# EasyEDApro.net
KiCad netlist of a schematic drawn in EasyEDA Pro
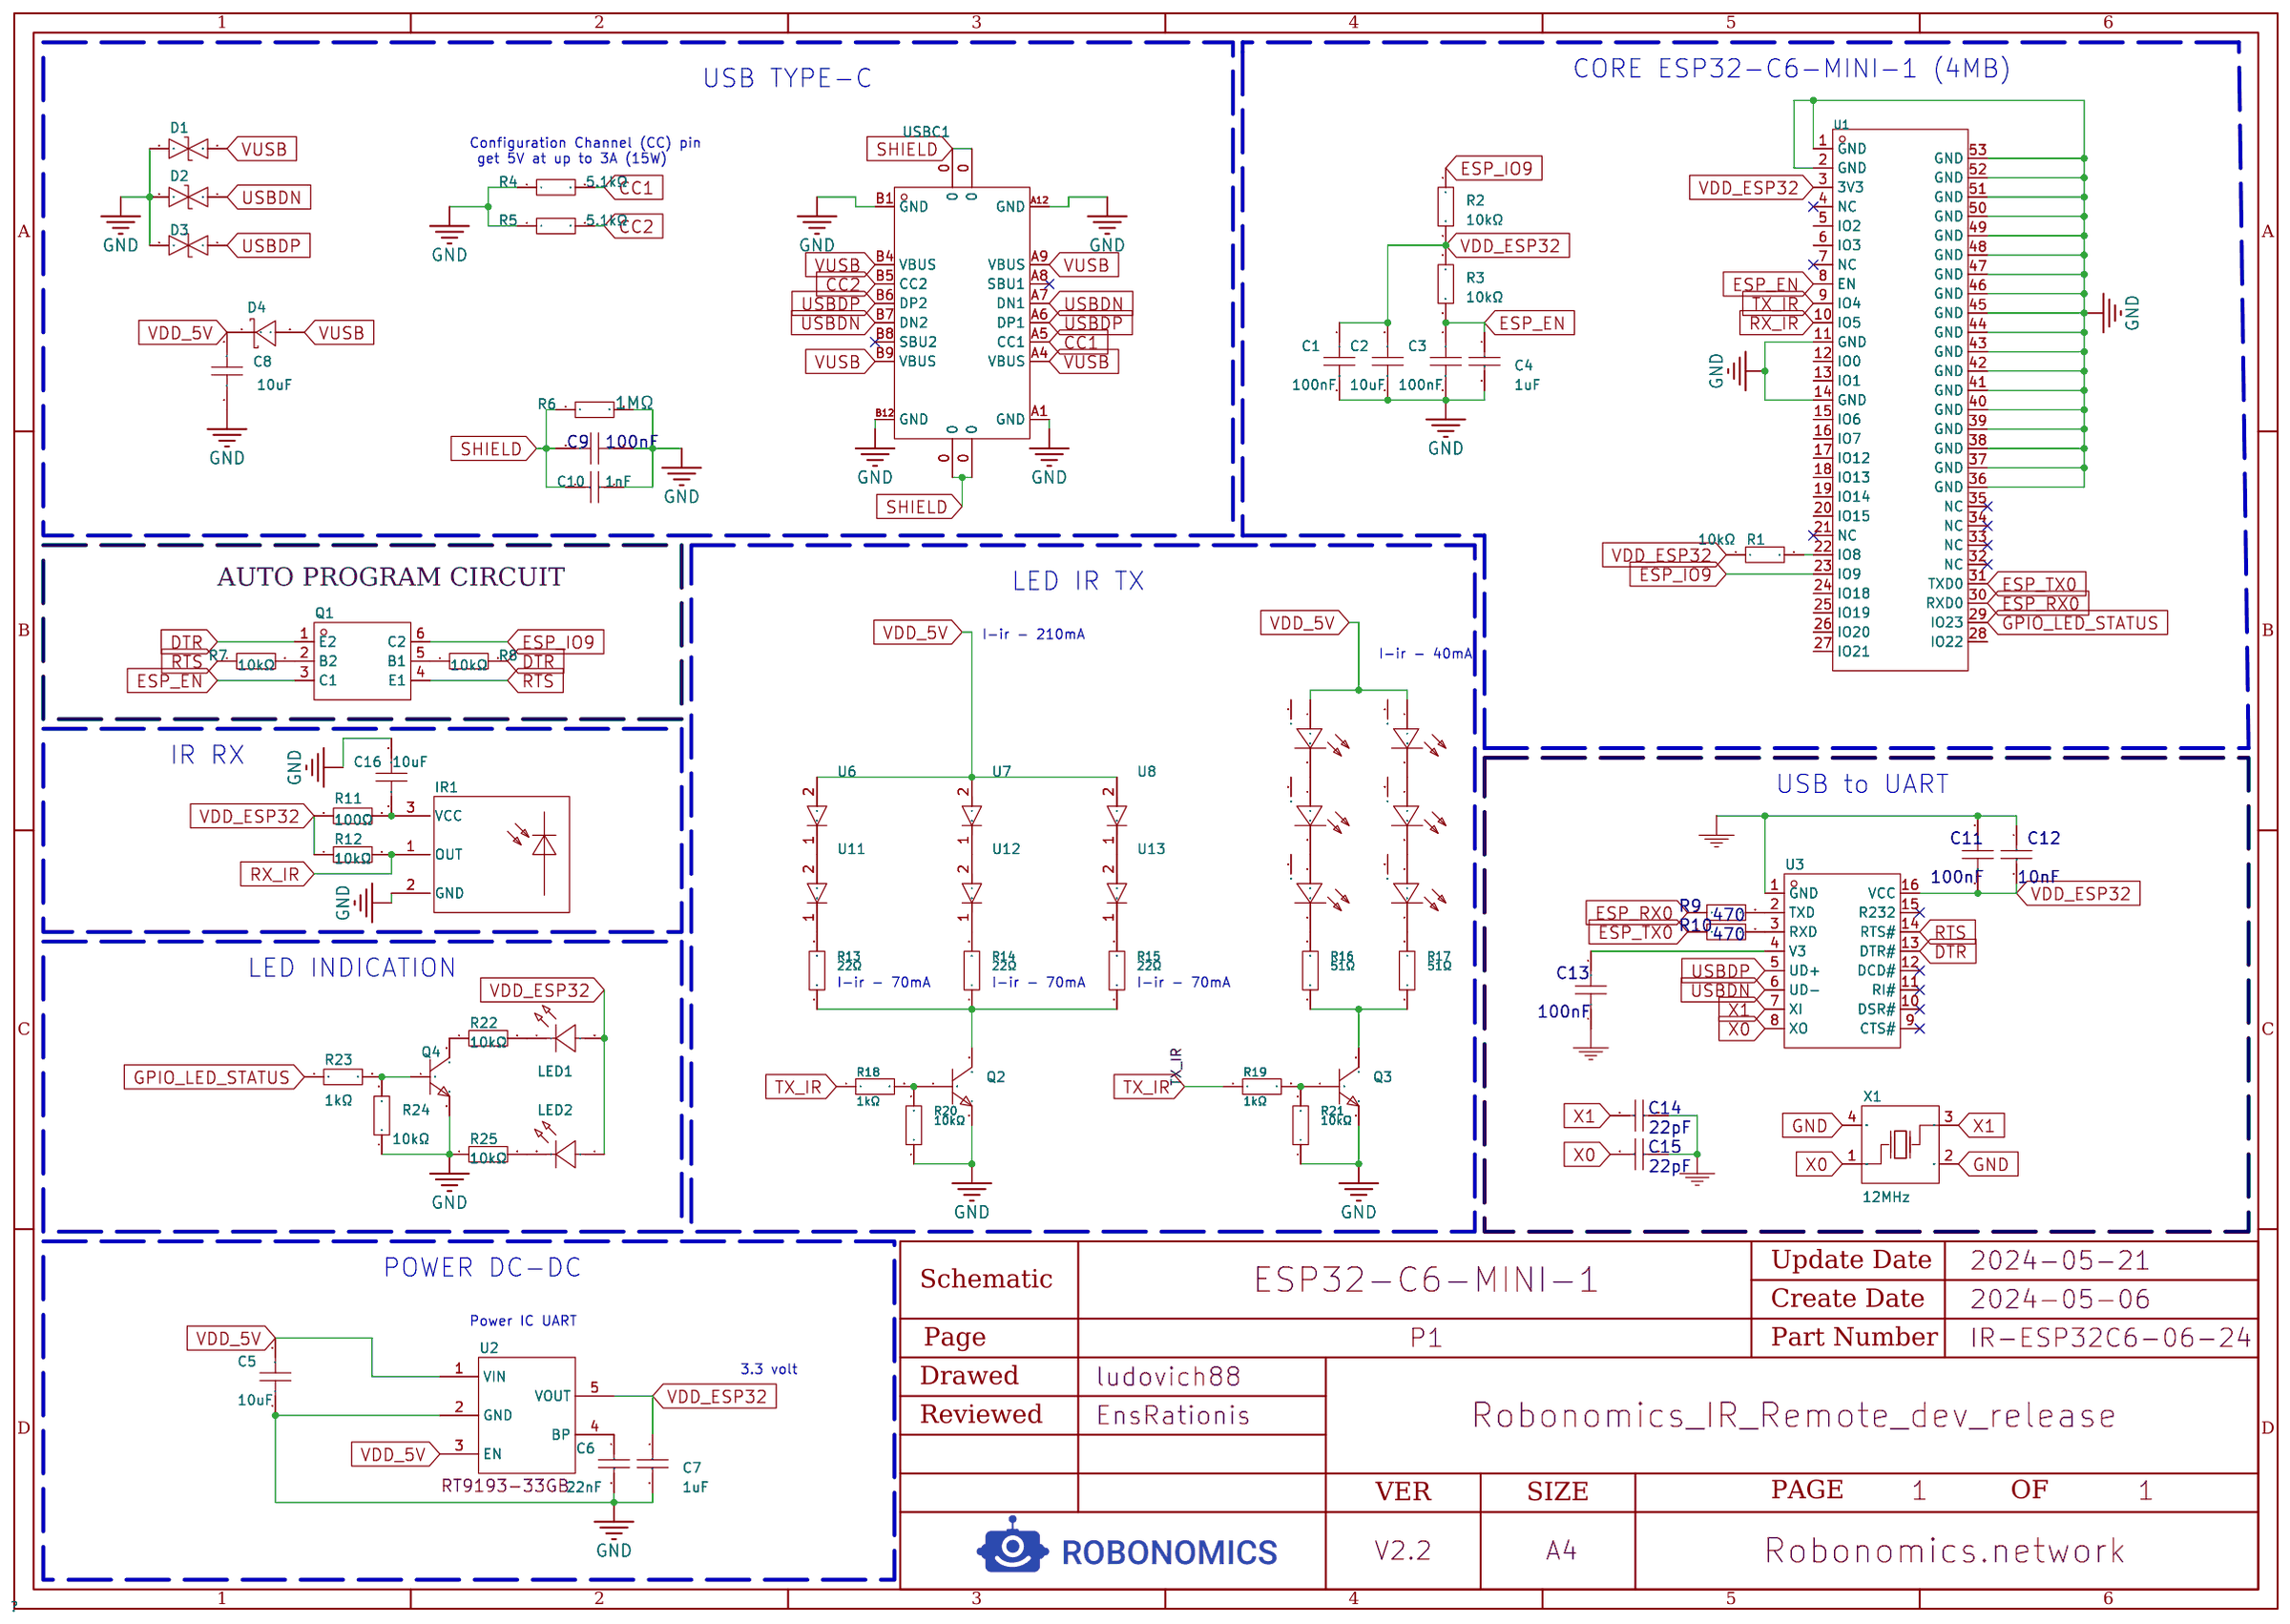
[diagram p0: schematic sheet]

(export (version "E")
  (design (tool "Eeschema 10.0.6"))
  (components
    (comp (ref "C1")
      (value "100nF")
      (fields
        (field (name "Manufacturer Part") "CC0603KRX7R9BB104")
        (field (name "Manufacturer") "YAGEO(国巨)")
      )
      (libsource (lib "easyedapro") (part "0603F104Z500"))
    )
    (comp (ref "C2")
      (value "10uF")
      (fields
        (field (name "Manufacturer Part") "CL10A106KP8NNNC")
        (field (name "Manufacturer") "SAMSUNG(三星)")
      )
      (libsource (lib "easyedapro") (part "CL10A106KP8NNNC"))
    )
    (comp (ref "C3")
      (value "100nF")
      (fields
        (field (name "Manufacturer Part") "CC0603KRX7R9BB104")
        (field (name "Manufacturer") "YAGEO(国巨)")
      )
      (libsource (lib "easyedapro") (part "0603F104Z500"))
    )
    (comp (ref "C4")
      (value "1uF")
      (footprint "easyedapro:C0603")
      (description "Capacitance:1uF Tolerance:±10% Tolerance:±10% Voltage Rated:50V Temperature Coefficient:X5R")
      (fields
        (field (name "Manufacturer Part") "CL10A105KB8NNNC")
        (field (name "Manufacturer") "SAMSUNG(三星)")
      )
      (libsource (lib "easyedapro") (part "CL10A105KB8NNNC"))
    )
    (comp (ref "C5")
      (value "10uF")
      (fields
        (field (name "Manufacturer Part") "CL10A106KP8NNNC")
        (field (name "Manufacturer") "SAMSUNG(三星)")
      )
      (libsource (lib "easyedapro") (part "CL10A106KP8NNNC"))
    )
    (comp (ref "C6")
      (value "22nF")
      (footprint "easyedapro:C0603")
      (description "Capacitance:22nF Tolerance:±10% Tolerance:±10% Voltage Rated:50V Temperature Coefficient:X7R")
      (fields
        (field (name "Manufacturer Part") "CL10B223KB8NNNC")
        (field (name "Manufacturer") "SAMSUNG(三星)")
      )
      (libsource (lib "easyedapro") (part "CL10B223KB8NNNC"))
    )
    (comp (ref "C7")
      (value "1uF")
      (footprint "easyedapro:C0603")
      (description "Capacitance:1uF Tolerance:±10% Tolerance:±10% Voltage Rated:50V Temperature Coefficient:X5R")
      (fields
        (field (name "Manufacturer Part") "CL10A105KB8NNNC")
        (field (name "Manufacturer") "SAMSUNG(三星)")
      )
      (libsource (lib "easyedapro") (part "CL10A105KB8NNNC"))
    )
    (comp (ref "C8")
      (value "10uF")
      (fields
        (field (name "Manufacturer Part") "CL10A106KP8NNNC")
        (field (name "Manufacturer") "SAMSUNG(三星)")
      )
      (libsource (lib "easyedapro") (part "CL10A106MA8NRNC"))
    )
    (comp (ref "C9")
      (value "100nF")
      (fields
        (field (name "Manufacturer Part") "CC0603KRX7R9BB104")
        (field (name "Manufacturer") "YAGEO(国巨)")
      )
      (libsource (lib "easyedapro") (part "100nF"))
    )
    (comp (ref "C10")
      (value "1nF")
      (footprint "easyedapro:C0603")
      (description "Capacitance:1nF Tolerance:±10% Tolerance:±10% Voltage Rated:50V Temperature Coefficient:X7R")
      (fields
        (field (name "Manufacturer Part") "CL10B102KB8NNNC")
        (field (name "Manufacturer") "SAMSUNG(三星)")
      )
      (libsource (lib "easyedapro") (part "CL10B102KB8NNNC"))
    )
    (comp (ref "C11")
      (value "100nF")
      (fields
        (field (name "Manufacturer Part") "CC0603KRX7R9BB104")
        (field (name "Manufacturer") "YAGEO(国巨)")
      )
      (libsource (lib "easyedapro") (part "100nF"))
    )
    (comp (ref "C12")
      (value "10nF")
      (footprint "easyedapro:C0603")
      (fields (field (name "Manufacturer Part") "0603B103K500NT") (field (name "Manufacturer") "FH"))
      (libsource (lib "easyedapro") (part "10nF"))
    )
    (comp (ref "C13")
      (value "100nF")
      (fields
        (field (name "Manufacturer Part") "CC0603KRX7R9BB104")
        (field (name "Manufacturer") "YAGEO(国巨)")
      )
      (libsource (lib "easyedapro") (part "100nF"))
    )
    (comp (ref "C14")
      (value "22pF")
      (footprint "easyedapro:C0603")
      (fields (field (name "Manufacturer Part") "CL10C220JB8NNNC") (field (name "Manufacturer") "SAMSUNG"))
      (libsource (lib "easyedapro") (part "22pF"))
    )
    (comp (ref "C15")
      (value "22pF")
      (footprint "easyedapro:C0603")
      (fields (field (name "Manufacturer Part") "CL10C220JB8NNNC") (field (name "Manufacturer") "SAMSUNG"))
      (libsource (lib "easyedapro") (part "22pF"))
    )
    (comp (ref "C16")
      (value "10uF")
      (fields
        (field (name "Manufacturer Part") "CL10A106KP8NNNC")
        (field (name "Manufacturer") "SAMSUNG(三星)")
      )
      (libsource (lib "easyedapro") (part "CL10A106KP8NNNC"))
    )
    (comp (ref "D1")
      (value "~")
      (footprint "easyedapro:SOD-523_L1.2-W0.8-LS1.6-BI")
      (fields (field (name "Manufacturer Part") "LESD5D5.0CT1G") (field (name "Manufacturer") "LRC(乐山无线电)"))
      (libsource (lib "easyedapro") (part "LESD5D5.0CT1G"))
    )
    (comp (ref "D2")
      (value "~")
      (footprint "easyedapro:SOD-523_L1.2-W0.8-LS1.6-BI")
      (fields (field (name "Manufacturer Part") "LESD5D5.0CT1G") (field (name "Manufacturer") "LRC(乐山无线电)"))
      (libsource (lib "easyedapro") (part "LESD5D5.0CT1G"))
    )
    (comp (ref "D3")
      (value "~")
      (footprint "easyedapro:SOD-523_L1.2-W0.8-LS1.6-BI")
      (fields (field (name "Manufacturer Part") "LESD5D5.0CT1G") (field (name "Manufacturer") "LRC(乐山无线电)"))
      (libsource (lib "easyedapro") (part "LESD5D5.0CT1G"))
    )
    (comp (ref "D4")
      (value "~")
      (footprint "easyedapro:SOD-123_L2.7-W1.6-LS3.7-RD")
      (description "Reverse Voltage (Vr):40V Average Rectified Current (Io):1A Forward Voltage (Vf@If):450mV@1A")
      (fields (field (name "Manufacturer Part") "1N5819HW-7-F") (field (name "Manufacturer") "DIODES(美台)"))
      (libsource (lib "easyedapro") (part "1N5819HW-7-F"))
    )
    (comp (ref "IR1")
      (value "~")
      (footprint "easyedapro:OPTO-TH_IRM-56384")
      (fields (field (name "Manufacturer Part") "IRM-56384") (field (name "Manufacturer") "EVERLIGHT(亿光)"))
      (libsource (lib "easyedapro") (part "IRM-56384"))
    )
    (comp (ref "LED1")
      (value "XL-4008UGC")
      (footprint "easyedapro:LED-SMD_L4.0-W1.4-RD_GREEN")
      (fields (field (name "Manufacturer") "XINGLIGHT(成兴光)"))
      (libsource (lib "easyedapro") (part "XL-4008UGC"))
    )
    (comp (ref "LED2")
      (value "XL-4008SURC")
      (footprint "easyedapro:LED-SMD_L4.0-W1.4-FD_C9900036310")
      (fields (field (name "Manufacturer") "XINGLIGHT(成兴光)"))
      (libsource (lib "easyedapro") (part "XL-4008SURC"))
    )
    (comp (ref "Q1")
      (value "~")
      (footprint "easyedapro:SOT-363_L2.0-W1.3-P0.65-LS2.1-BR")
      (fields (field (name "Manufacturer Part") "LBC847BDW1T1G") (field (name "Manufacturer") "LRC(乐山无线电)"))
      (libsource (lib "easyedapro") (part "LBC847BDW1T1G"))
    )
    (comp (ref "Q2")
      (value "~")
      (footprint "easyedapro:SOT-23-3_L2.9-W1.6-P1.90-LS2.8-BR")
      (fields (field (name "Manufacturer Part") "SS8050") (field (name "Manufacturer") "CJ(江苏长电/长晶)"))
      (libsource (lib "easyedapro") (part "SS8050_C177739"))
    )
    (comp (ref "Q3")
      (value "~")
      (footprint "easyedapro:SOT-23-3_L2.9-W1.6-P1.90-LS2.8-BR")
      (fields (field (name "Manufacturer Part") "SS8050") (field (name "Manufacturer") "CJ(江苏长电/长晶)"))
      (libsource (lib "easyedapro") (part "SS8050_C177739"))
    )
    (comp (ref "Q4")
      (value "SS8050")
      (footprint "easyedapro:SOT-23-3_L2.9-W1.6-P1.90-LS2.8-BR")
      (fields (field (name "Manufacturer") "Hottech(合科泰)"))
      (libsource (lib "easyedapro") (part "SS8050_C181160"))
    )
    (comp (ref "R1")
      (value "10kΩ")
      (fields
        (field (name "Manufacturer Part") "0603WAF1002T5E")
        (field (name "Manufacturer") "UNI-ROYAL(厚声)")
      )
      (libsource (lib "easyedapro") (part "0603WAF1002T5E"))
    )
    (comp (ref "R2")
      (value "10kΩ")
      (fields
        (field (name "Manufacturer Part") "0603WAF1002T5E")
        (field (name "Manufacturer") "UNI-ROYAL(厚声)")
      )
      (libsource (lib "easyedapro") (part "0603WAF1002T5E"))
    )
    (comp (ref "R3")
      (value "10kΩ")
      (fields
        (field (name "Manufacturer Part") "0603WAF1002T5E")
        (field (name "Manufacturer") "UNI-ROYAL(厚声)")
      )
      (libsource (lib "easyedapro") (part "0603WAF1002T5E"))
    )
    (comp (ref "R4")
      (value "5.1kΩ")
      (footprint "easyedapro:R0603")
      (fields
        (field (name "Manufacturer Part") "0603WAF5101T5E")
        (field (name "Manufacturer") "UNI-ROYAL(厚声)")
      )
      (libsource (lib "easyedapro") (part "0603WAF5101T5E"))
    )
    (comp (ref "R5")
      (value "5.1kΩ")
      (footprint "easyedapro:R0603")
      (fields
        (field (name "Manufacturer Part") "0603WAF5101T5E")
        (field (name "Manufacturer") "UNI-ROYAL(厚声)")
      )
      (libsource (lib "easyedapro") (part "0603WAF5101T5E"))
    )
    (comp (ref "R6")
      (value "1MΩ")
      (footprint "easyedapro:R0603")
      (fields
        (field (name "Manufacturer Part") "0603WAF1004T5E")
        (field (name "Manufacturer") "UNI-ROYAL(厚声)")
      )
      (libsource (lib "easyedapro") (part "0603WAF1004T5E"))
    )
    (comp (ref "R7")
      (value "10kΩ")
      (fields
        (field (name "Manufacturer Part") "0603WAF1002T5E")
        (field (name "Manufacturer") "UNI-ROYAL(厚声)")
      )
      (libsource (lib "easyedapro") (part "0603WAF1002T5E"))
    )
    (comp (ref "R8")
      (value "10kΩ")
      (fields
        (field (name "Manufacturer Part") "0603WAF1002T5E")
        (field (name "Manufacturer") "UNI-ROYAL(厚声)")
      )
      (libsource (lib "easyedapro") (part "0603WAF1002T5E"))
    )
    (comp (ref "R9")
      (value "470Ω")
      (footprint "easyedapro:R0603")
      (fields (field (name "Manufacturer Part") "0603WAF4700T5E") (field (name "Manufacturer") "UniOhm"))
      (libsource (lib "easyedapro") (part "470"))
    )
    (comp (ref "R10")
      (value "470Ω")
      (footprint "easyedapro:R0603")
      (fields (field (name "Manufacturer Part") "0603WAF4700T5E") (field (name "Manufacturer") "UniOhm"))
      (libsource (lib "easyedapro") (part "470"))
    )
    (comp (ref "R11")
      (value "100Ω")
      (footprint "easyedapro:R0603")
      (fields
        (field (name "Manufacturer Part") "0603WAF1000T5E")
        (field (name "Manufacturer") "UNI-ROYAL(厚声)")
      )
      (libsource (lib "easyedapro") (part "0603WAF1000T5E"))
    )
    (comp (ref "R12")
      (value "10kΩ")
      (fields
        (field (name "Manufacturer Part") "0603WAF1002T5E")
        (field (name "Manufacturer") "UNI-ROYAL(厚声)")
      )
      (libsource (lib "easyedapro") (part "0603WAF1002T5E"))
    )
    (comp (ref "R13")
      (value "22Ω")
      (footprint "easyedapro:R0603")
      (fields
        (field (name "Manufacturer Part") "0603WAF220JT5E")
        (field (name "Manufacturer") "UNI-ROYAL(厚声)")
      )
      (libsource (lib "easyedapro") (part "0603WAF220JT5E"))
    )
    (comp (ref "R14")
      (value "22Ω")
      (footprint "easyedapro:R0603")
      (fields
        (field (name "Manufacturer Part") "0603WAF220JT5E")
        (field (name "Manufacturer") "UNI-ROYAL(厚声)")
      )
      (libsource (lib "easyedapro") (part "0603WAF220JT5E"))
    )
    (comp (ref "R15")
      (value "22Ω")
      (footprint "easyedapro:R0603")
      (fields
        (field (name "Manufacturer Part") "0603WAF220JT5E")
        (field (name "Manufacturer") "UNI-ROYAL(厚声)")
      )
      (libsource (lib "easyedapro") (part "0603WAF220JT5E"))
    )
    (comp (ref "R16")
      (value "51Ω")
      (footprint "easyedapro:R0603")
      (fields
        (field (name "Manufacturer Part") "0603WAF510JT5E")
        (field (name "Manufacturer") "UNI-ROYAL(厚声)")
      )
      (libsource (lib "easyedapro") (part "0603WAF510JT5E"))
    )
    (comp (ref "R17")
      (value "51Ω")
      (footprint "easyedapro:R0603")
      (fields
        (field (name "Manufacturer Part") "0603WAF510JT5E")
        (field (name "Manufacturer") "UNI-ROYAL(厚声)")
      )
      (libsource (lib "easyedapro") (part "0603WAF510JT5E"))
    )
    (comp (ref "R18")
      (value "1kΩ")
      (footprint "easyedapro:R0603")
      (fields
        (field (name "Manufacturer Part") "0603WAF1001T5E")
        (field (name "Manufacturer") "UNI-ROYAL(厚声)")
      )
      (libsource (lib "easyedapro") (part "0603WAF1001T5E"))
    )
    (comp (ref "R19")
      (value "1kΩ")
      (footprint "easyedapro:R0603")
      (fields
        (field (name "Manufacturer Part") "0603WAF1001T5E")
        (field (name "Manufacturer") "UNI-ROYAL(厚声)")
      )
      (libsource (lib "easyedapro") (part "0603WAF1001T5E"))
    )
    (comp (ref "R20")
      (value "10kΩ")
      (footprint "easyedapro:R0603")
      (fields
        (field (name "Manufacturer Part") "0603WAF1002T5E")
        (field (name "Manufacturer") "UNI-ROYAL(厚声)")
      )
      (libsource (lib "easyedapro") (part "0603WAF1002T5E"))
    )
    (comp (ref "R21")
      (value "10kΩ")
      (footprint "easyedapro:R0603")
      (fields
        (field (name "Manufacturer Part") "0603WAF1002T5E")
        (field (name "Manufacturer") "UNI-ROYAL(厚声)")
      )
      (libsource (lib "easyedapro") (part "0603WAF1002T5E"))
    )
    (comp (ref "R22")
      (value "10kΩ")
      (fields
        (field (name "Manufacturer Part") "0603WAF1002T5E")
        (field (name "Manufacturer") "UNI-ROYAL(厚声)")
      )
      (libsource (lib "easyedapro") (part "0603WAF1002T5E"))
    )
    (comp (ref "R23")
      (value "1kΩ")
      (footprint "easyedapro:R0603")
      (fields (field (name "Manufacturer Part") "RC0603FR-071KL") (field (name "Manufacturer") "YAGEO(国巨)"))
      (libsource (lib "easyedapro") (part "RC0603FR-071KL"))
    )
    (comp (ref "R24")
      (value "10kΩ")
      (fields
        (field (name "Manufacturer Part") "0603WAF1002T5E")
        (field (name "Manufacturer") "UNI-ROYAL(厚声)")
      )
      (libsource (lib "easyedapro") (part "0603WAF1002T5E"))
    )
    (comp (ref "R25")
      (value "10kΩ")
      (fields
        (field (name "Manufacturer Part") "0603WAF1002T5E")
        (field (name "Manufacturer") "UNI-ROYAL(厚声)")
      )
      (libsource (lib "easyedapro") (part "0603WAF1002T5E"))
    )
    (comp (ref "U1")
      (value "ESP32-C6-MINI-1-N4")
      (footprint "easyedapro:WIFIM-SMD_61P-L16.6-W13.2-P0.80-ESP32-C6-MINI-1-N4")
      (fields (field (name "Manufacturer") "ESPRESSIF(乐鑫)"))
      (libsource (lib "easyedapro") (part "ESP32-C6-MINI-1-N4"))
    )
    (comp (ref "U2")
      (value "~")
      (footprint "easyedapro:SOT-23-5_L3.0-W1.7-P0.95-LS2.8-BR")
      (fields (field (name "Manufacturer Part") "RT9193-33GB") (field (name "Manufacturer") "RICHTEK(台湾立锜)"))
      (libsource (lib "easyedapro") (part "RT9193-33GB"))
    )
    (comp (ref "U3")
      (value "~")
      (footprint "easyedapro:SOIC-16_L9.9-W3.9-P1.27-LS6.0-BL")
      (fields (field (name "Manufacturer Part") "CH340G") (field (name "Manufacturer") "WCH(南京沁恒)"))
      (libsource (lib "easyedapro") (part "CH340G"))
    )
    (comp (ref "U4")
      (value "LKIR30102C-A01(XY)")
      (footprint "easyedapro:LED-SMD_EVERLIGHT_LKIR30102C-A01XY")
      (fields (field (name "Manufacturer") "EVERLIGHT(亿光)"))
      (libsource (lib "easyedapro") (part "LKIR30102C-A01(XY)"))
    )
    (comp (ref "U5")
      (value "LKIR30102C-A01(XY)")
      (footprint "easyedapro:LED-SMD_EVERLIGHT_LKIR30102C-A01XY")
      (fields (field (name "Manufacturer") "EVERLIGHT(亿光)"))
      (libsource (lib "easyedapro") (part "LKIR30102C-A01(XY)"))
    )
    (comp (ref "U6")
      (value "SFH 4253-Z")
      (footprint "easyedapro:OPTO-SMD_L3.2-W2.8-LS3.5-L-1")
      (fields (field (name "Manufacturer") "OSRAM(欧司朗)"))
      (libsource (lib "easyedapro") (part "SFH 4253-Z"))
    )
    (comp (ref "U7")
      (value "SFH 4253-Z")
      (footprint "easyedapro:OPTO-SMD_L3.2-W2.8-LS3.5-L-1")
      (fields (field (name "Manufacturer") "OSRAM(欧司朗)"))
      (libsource (lib "easyedapro") (part "SFH 4253-Z"))
    )
    (comp (ref "U8")
      (value "SFH 4253-Z")
      (footprint "easyedapro:OPTO-SMD_L3.2-W2.8-LS3.5-L-1")
      (fields (field (name "Manufacturer") "OSRAM(欧司朗)"))
      (libsource (lib "easyedapro") (part "SFH 4253-Z"))
    )
    (comp (ref "U9")
      (value "LKIR30102C-A01(XY)")
      (footprint "easyedapro:LED-SMD_EVERLIGHT_LKIR30102C-A01XY")
      (fields (field (name "Manufacturer") "EVERLIGHT(亿光)"))
      (libsource (lib "easyedapro") (part "LKIR30102C-A01(XY)"))
    )
    (comp (ref "U10")
      (value "LKIR30102C-A01(XY)")
      (footprint "easyedapro:LED-SMD_EVERLIGHT_LKIR30102C-A01XY")
      (fields (field (name "Manufacturer") "EVERLIGHT(亿光)"))
      (libsource (lib "easyedapro") (part "LKIR30102C-A01(XY)"))
    )
    (comp (ref "U11")
      (value "SFH 4253-Z")
      (footprint "easyedapro:OPTO-SMD_L3.2-W2.8-LS3.5-L-1")
      (fields (field (name "Manufacturer") "OSRAM(欧司朗)"))
      (libsource (lib "easyedapro") (part "SFH 4253-Z"))
    )
    (comp (ref "U12")
      (value "SFH 4253-Z")
      (footprint "easyedapro:OPTO-SMD_L3.2-W2.8-LS3.5-L-1")
      (fields (field (name "Manufacturer") "OSRAM(欧司朗)"))
      (libsource (lib "easyedapro") (part "SFH 4253-Z"))
    )
    (comp (ref "U13")
      (value "SFH 4253-Z")
      (footprint "easyedapro:OPTO-SMD_L3.2-W2.8-LS3.5-L-1")
      (fields (field (name "Manufacturer") "OSRAM(欧司朗)"))
      (libsource (lib "easyedapro") (part "SFH 4253-Z"))
    )
    (comp (ref "U14")
      (value "LKIR30102C-A01(XY)")
      (footprint "easyedapro:LED-SMD_EVERLIGHT_LKIR30102C-A01XY")
      (fields (field (name "Manufacturer") "EVERLIGHT(亿光)"))
      (libsource (lib "easyedapro") (part "LKIR30102C-A01(XY)"))
    )
    (comp (ref "U15")
      (value "LKIR30102C-A01(XY)")
      (footprint "easyedapro:LED-SMD_EVERLIGHT_LKIR30102C-A01XY")
      (fields (field (name "Manufacturer") "EVERLIGHT(亿光)"))
      (libsource (lib "easyedapro") (part "LKIR30102C-A01(XY)"))
    )
    (comp (ref "USBC1")
      (value "~")
      (footprint "easyedapro:USB-C_SMD-TYPE-C-31-M-12")
      (fields (field (name "Manufacturer Part") "TYPE-C-31-M-12") (field (name "Manufacturer") "韩国韩荣"))
      (libsource (lib "easyedapro") (part "TYPE-C-31-M-12"))
    )
    (comp (ref "X1")
      (value "12MHz")
      (footprint "easyedapro:OSC-SMD_4P-L3.2-W2.5-BL")
      (fields (field (name "Manufacturer Part") "X322512MSB4SI") (field (name "Manufacturer") "YXC扬兴科技"))
      (libsource (lib "easyedapro") (part "X322512MSB4SI"))
    )
  )
  (nets
    (net (code "1") (name "CC1") (class "Default")
      (node (ref "R4") (pin "2") (pinfunction "2_2") (pintype "input"))
      (node (ref "USBC1") (pin "A5") (pinfunction "CC1_A5") (pintype "input"))
    )
    (net (code "2") (name "CC2") (class "Default")
      (node (ref "R5") (pin "2") (pinfunction "2_2") (pintype "input"))
      (node (ref "USBC1") (pin "B5") (pinfunction "CC2_B5") (pintype "input"))
    )
    (net (code "3") (name "DTR") (class "Default")
      (node (ref "Q1") (pin "1") (pinfunction "E2_1") (pintype "input"))
      (node (ref "R8") (pin "2") (pinfunction "2_2") (pintype "input"))
      (node (ref "U3") (pin "13") (pinfunction "DTR#_13") (pintype "input"))
    )
    (net (code "4") (name "ESP_EN") (class "Default")
      (node (ref "C3") (pin "1") (pinfunction "1_1") (pintype "input"))
      (node (ref "C4") (pin "1") (pinfunction "1_1") (pintype "input"))
      (node (ref "Q1") (pin "3") (pinfunction "C1_3") (pintype "input"))
      (node (ref "R3") (pin "2") (pinfunction "2_2") (pintype "input"))
      (node (ref "U1") (pin "8") (pinfunction "EN_8") (pintype "input"))
    )
    (net (code "5") (name "ESP_IO9") (class "Default")
      (node (ref "Q1") (pin "6") (pinfunction "C2_6") (pintype "input"))
      (node (ref "R2") (pin "1") (pinfunction "1_1") (pintype "input"))
      (node (ref "U1") (pin "23") (pinfunction "IO9_23") (pintype "input"))
    )
    (net (code "6") (name "ESP_RX0") (class "Default")
      (node (ref "R9") (pin "1") (pinfunction "1_1") (pintype "input"))
      (node (ref "U1") (pin "30") (pinfunction "RXD0_30") (pintype "input"))
    )
    (net (code "7") (name "ESP_TX0") (class "Default")
      (node (ref "R10") (pin "1") (pinfunction "1_1") (pintype "input"))
      (node (ref "U1") (pin "31") (pinfunction "TXD0_31") (pintype "input"))
    )
    (net (code "8") (name "GND") (class "Default")
      (node (ref "C1") (pin "2") (pinfunction "2_2") (pintype "input"))
      (node (ref "C10") (pin "2") (pinfunction "2_2") (pintype "input"))
      (node (ref "C11") (pin "1") (pinfunction "1_1") (pintype "input"))
      (node (ref "C12") (pin "1") (pinfunction "1_1") (pintype "input"))
      (node (ref "C13") (pin "1") (pinfunction "1_1") (pintype "input"))
      (node (ref "C14") (pin "1") (pinfunction "1_1") (pintype "input"))
      (node (ref "C15") (pin "1") (pinfunction "1_1") (pintype "input"))
      (node (ref "C16") (pin "2") (pinfunction "2_2") (pintype "input"))
      (node (ref "C2") (pin "1") (pinfunction "1_1") (pintype "input"))
      (node (ref "C3") (pin "2") (pinfunction "2_2") (pintype "input"))
      (node (ref "C4") (pin "2") (pinfunction "2_2") (pintype "input"))
      (node (ref "C5") (pin "1") (pinfunction "1_1") (pintype "input"))
      (node (ref "C6") (pin "2") (pinfunction "2_2") (pintype "input"))
      (node (ref "C7") (pin "2") (pinfunction "2_2") (pintype "input"))
      (node (ref "C8") (pin "1") (pinfunction "1_1") (pintype "input"))
      (node (ref "C9") (pin "1") (pinfunction "1_1") (pintype "input"))
      (node (ref "D1") (pin "2") (pinfunction "2_2") (pintype "input"))
      (node (ref "D2") (pin "2") (pinfunction "2_2") (pintype "input"))
      (node (ref "D3") (pin "2") (pinfunction "2_2") (pintype "input"))
      (node (ref "IR1") (pin "2") (pinfunction "GND_2") (pintype "input"))
      (node (ref "Q2") (pin "2") (pinfunction "E_2") (pintype "input"))
      (node (ref "Q3") (pin "2") (pinfunction "E_2") (pintype "input"))
      (node (ref "Q4") (pin "2") (pinfunction "E_2") (pintype "input"))
      (node (ref "R20") (pin "1") (pinfunction "1_1") (pintype "input"))
      (node (ref "R21") (pin "1") (pinfunction "1_1") (pintype "input"))
      (node (ref "R24") (pin "1") (pinfunction "1_1") (pintype "input"))
      (node (ref "R25") (pin "1") (pinfunction "1_1") (pintype "input"))
      (node (ref "R4") (pin "1") (pinfunction "1_1") (pintype "input"))
      (node (ref "R5") (pin "1") (pinfunction "1_1") (pintype "input"))
      (node (ref "R6") (pin "2") (pinfunction "2_2") (pintype "input"))
      (node (ref "U1") (pin "1") (pinfunction "GND_1") (pintype "input"))
      (node (ref "U1") (pin "11") (pinfunction "GND_11") (pintype "input"))
      (node (ref "U1") (pin "14") (pinfunction "GND_14") (pintype "input"))
      (node (ref "U1") (pin "2") (pinfunction "GND_2") (pintype "input"))
      (node (ref "U1") (pin "36") (pinfunction "GND_36") (pintype "input"))
      (node (ref "U1") (pin "37") (pinfunction "GND_37") (pintype "input"))
      (node (ref "U1") (pin "38") (pinfunction "GND_38") (pintype "input"))
      (node (ref "U1") (pin "39") (pinfunction "GND_39") (pintype "input"))
      (node (ref "U1") (pin "40") (pinfunction "GND_40") (pintype "input"))
      (node (ref "U1") (pin "41") (pinfunction "GND_41") (pintype "input"))
      (node (ref "U1") (pin "42") (pinfunction "GND_42") (pintype "input"))
      (node (ref "U1") (pin "43") (pinfunction "GND_43") (pintype "input"))
      (node (ref "U1") (pin "44") (pinfunction "GND_44") (pintype "input"))
      (node (ref "U1") (pin "45") (pinfunction "GND_45") (pintype "input"))
      (node (ref "U1") (pin "46") (pinfunction "GND_46") (pintype "input"))
      (node (ref "U1") (pin "47") (pinfunction "GND_47") (pintype "input"))
      (node (ref "U1") (pin "48") (pinfunction "GND_48") (pintype "input"))
      (node (ref "U1") (pin "49") (pinfunction "GND_49") (pintype "input"))
      (node (ref "U1") (pin "50") (pinfunction "GND_50") (pintype "input"))
      (node (ref "U1") (pin "51") (pinfunction "GND_51") (pintype "input"))
      (node (ref "U1") (pin "52") (pinfunction "GND_52") (pintype "input"))
      (node (ref "U1") (pin "53") (pinfunction "GND_53") (pintype "input"))
      (node (ref "U2") (pin "2") (pinfunction "GND_2") (pintype "input"))
      (node (ref "U3") (pin "1") (pinfunction "GND_1") (pintype "input"))
      (node (ref "USBC1") (pin "A1") (pinfunction "GND_A1") (pintype "input"))
      (node (ref "USBC1") (pin "A12") (pinfunction "GND_A12") (pintype "input"))
      (node (ref "USBC1") (pin "B1") (pinfunction "GND_B1") (pintype "input"))
      (node (ref "USBC1") (pin "B12") (pinfunction "GND_B12") (pintype "input"))
      (node (ref "X1") (pin "2") (pinfunction "GND_2") (pintype "input"))
      (node (ref "X1") (pin "4") (pinfunction "GND_4") (pintype "input"))
    )
    (net (code "9") (name "GPIO_LED_STATUS") (class "Default")
      (node (ref "R23") (pin "1") (pinfunction "1_1") (pintype "input"))
      (node (ref "U1") (pin "29") (pinfunction "IO23_29") (pintype "input"))
    )
    (net (code "10") (name "Net-(IR1-VCC)") (class "Default")
      (node (ref "C16") (pin "1") (pinfunction "1_1") (pintype "input"))
      (node (ref "IR1") (pin "3") (pinfunction "VCC_3") (pintype "input"))
      (node (ref "R11") (pin "2") (pinfunction "2_2") (pintype "input"))
    )
    (net (code "11") (name "Net-(LED1-K)") (class "Default")
      (node (ref "LED1") (pin "1") (pinfunction "K_1") (pintype "input"))
      (node (ref "R22") (pin "2") (pinfunction "2_2") (pintype "input"))
    )
    (net (code "12") (name "Net-(LED2-K)") (class "Default")
      (node (ref "LED2") (pin "2") (pinfunction "K_2") (pintype "input"))
      (node (ref "R25") (pin "2") (pinfunction "2_2") (pintype "input"))
    )
    (net (code "13") (name "Net-(Q1-B1)") (class "Default")
      (node (ref "Q1") (pin "5") (pinfunction "B1_5") (pintype "input"))
      (node (ref "R8") (pin "1") (pinfunction "1_1") (pintype "input"))
    )
    (net (code "14") (name "Net-(Q1-B2)") (class "Default")
      (node (ref "Q1") (pin "2") (pinfunction "B2_2") (pintype "input"))
      (node (ref "R7") (pin "2") (pinfunction "2_2") (pintype "input"))
    )
    (net (code "15") (name "Net-(Q2-B)") (class "Default")
      (node (ref "Q2") (pin "1") (pinfunction "B_1") (pintype "input"))
      (node (ref "R18") (pin "2") (pinfunction "2_2") (pintype "input"))
      (node (ref "R20") (pin "2") (pinfunction "2_2") (pintype "input"))
    )
    (net (code "16") (name "Net-(Q2-C)") (class "Default")
      (node (ref "Q2") (pin "3") (pinfunction "C_3") (pintype "input"))
      (node (ref "R13") (pin "1") (pinfunction "1_1") (pintype "input"))
      (node (ref "R14") (pin "1") (pinfunction "1_1") (pintype "input"))
      (node (ref "R15") (pin "1") (pinfunction "1_1") (pintype "input"))
    )
    (net (code "17") (name "Net-(Q3-B)") (class "Default")
      (node (ref "Q3") (pin "1") (pinfunction "B_1") (pintype "input"))
      (node (ref "R19") (pin "2") (pinfunction "2_2") (pintype "input"))
      (node (ref "R21") (pin "2") (pinfunction "2_2") (pintype "input"))
    )
    (net (code "18") (name "Net-(Q3-C)") (class "Default")
      (node (ref "Q3") (pin "3") (pinfunction "C_3") (pintype "input"))
      (node (ref "R16") (pin "1") (pinfunction "1_1") (pintype "input"))
      (node (ref "R17") (pin "1") (pinfunction "1_1") (pintype "input"))
    )
    (net (code "19") (name "Net-(Q4-B)") (class "Default")
      (node (ref "Q4") (pin "1") (pinfunction "B_1") (pintype "input"))
      (node (ref "R23") (pin "2") (pinfunction "2_2") (pintype "input"))
      (node (ref "R24") (pin "2") (pinfunction "2_2") (pintype "input"))
    )
    (net (code "20") (name "Net-(Q4-C)") (class "Default")
      (node (ref "Q4") (pin "3") (pinfunction "C_3") (pintype "input"))
      (node (ref "R22") (pin "1") (pinfunction "1_1") (pintype "input"))
    )
    (net (code "21") (name "Net-(U1-IO8)") (class "Default")
      (node (ref "R1") (pin "2") (pinfunction "2_2") (pintype "input"))
      (node (ref "U1") (pin "22") (pinfunction "IO8_22") (pintype "input"))
    )
    (net (code "22") (name "Net-(U2-BP)") (class "Default")
      (node (ref "C6") (pin "1") (pinfunction "1_1") (pintype "input"))
      (node (ref "U2") (pin "4") (pinfunction "BP_4") (pintype "input"))
    )
    (net (code "23") (name "Net-(U3-RXD)") (class "Default")
      (node (ref "R10") (pin "2") (pinfunction "2_2") (pintype "input"))
      (node (ref "U3") (pin "3") (pinfunction "RXD_3") (pintype "input"))
    )
    (net (code "24") (name "Net-(U3-TXD)") (class "Default")
      (node (ref "R9") (pin "2") (pinfunction "2_2") (pintype "input"))
      (node (ref "U3") (pin "2") (pinfunction "TXD_2") (pintype "input"))
    )
    (net (code "25") (name "Net-(U3-V3)") (class "Default")
      (node (ref "C13") (pin "2") (pinfunction "2_2") (pintype "input"))
      (node (ref "U3") (pin "4") (pinfunction "V3_4") (pintype "input"))
    )
    (net (code "26") (name "Net-(U4-C)") (class "Default")
      (node (ref "U4") (pin "2") (pinfunction "C_2") (pintype "input"))
      (node (ref "U9") (pin "1") (pinfunction "A_1") (pintype "input"))
    )
    (net (code "27") (name "Net-(U10-A)") (class "Default")
      (node (ref "U10") (pin "1") (pinfunction "A_1") (pintype "input"))
      (node (ref "U5") (pin "2") (pinfunction "C_2") (pintype "input"))
    )
    (net (code "28") (name "Net-(U10-C)") (class "Default")
      (node (ref "U10") (pin "2") (pinfunction "C_2") (pintype "input"))
      (node (ref "U15") (pin "1") (pinfunction "A_1") (pintype "input"))
    )
    (net (code "29") (name "Net-(U11-A)") (class "Default")
      (node (ref "U11") (pin "2") (pinfunction "A_2") (pintype "input"))
      (node (ref "U6") (pin "1") (pinfunction "C_1") (pintype "input"))
    )
    (net (code "30") (name "Net-(U11-C)") (class "Default")
      (node (ref "R13") (pin "2") (pinfunction "2_2") (pintype "input"))
      (node (ref "U11") (pin "1") (pinfunction "C_1") (pintype "input"))
    )
    (net (code "31") (name "Net-(U12-A)") (class "Default")
      (node (ref "U12") (pin "2") (pinfunction "A_2") (pintype "input"))
      (node (ref "U7") (pin "1") (pinfunction "C_1") (pintype "input"))
    )
    (net (code "32") (name "Net-(U12-C)") (class "Default")
      (node (ref "R14") (pin "2") (pinfunction "2_2") (pintype "input"))
      (node (ref "U12") (pin "1") (pinfunction "C_1") (pintype "input"))
    )
    (net (code "33") (name "Net-(U13-A)") (class "Default")
      (node (ref "U13") (pin "2") (pinfunction "A_2") (pintype "input"))
      (node (ref "U8") (pin "1") (pinfunction "C_1") (pintype "input"))
    )
    (net (code "34") (name "Net-(U13-C)") (class "Default")
      (node (ref "R15") (pin "2") (pinfunction "2_2") (pintype "input"))
      (node (ref "U13") (pin "1") (pinfunction "C_1") (pintype "input"))
    )
    (net (code "35") (name "Net-(U14-A)") (class "Default")
      (node (ref "U14") (pin "1") (pinfunction "A_1") (pintype "input"))
      (node (ref "U9") (pin "2") (pinfunction "C_2") (pintype "input"))
    )
    (net (code "36") (name "Net-(U14-C)") (class "Default")
      (node (ref "R16") (pin "2") (pinfunction "2_2") (pintype "input"))
      (node (ref "U14") (pin "2") (pinfunction "C_2") (pintype "input"))
    )
    (net (code "37") (name "Net-(U15-C)") (class "Default")
      (node (ref "R17") (pin "2") (pinfunction "2_2") (pintype "input"))
      (node (ref "U15") (pin "2") (pinfunction "C_2") (pintype "input"))
    )
    (net (code "38") (name "RTS") (class "Default")
      (node (ref "Q1") (pin "4") (pinfunction "E1_4") (pintype "input"))
      (node (ref "R7") (pin "1") (pinfunction "1_1") (pintype "input"))
      (node (ref "U3") (pin "14") (pinfunction "RTS#_14") (pintype "input"))
    )
    (net (code "39") (name "RX_IR") (class "Default")
      (node (ref "IR1") (pin "1") (pinfunction "OUT_1") (pintype "input"))
      (node (ref "R12") (pin "2") (pinfunction "2_2") (pintype "input"))
      (node (ref "U1") (pin "10") (pinfunction "IO5_10") (pintype "input"))
    )
    (net (code "40") (name "SHIELD") (class "Default")
      (node (ref "C10") (pin "1") (pinfunction "1_1") (pintype "input"))
      (node (ref "C9") (pin "2") (pinfunction "2_2") (pintype "input"))
      (node (ref "R6") (pin "1") (pinfunction "1_1") (pintype "input"))
      (node (ref "USBC1") (pin "0") (pinfunction "0_0") (pintype "input"))
    )
    (net (code "41") (name "TX_IR") (class "Default")
      (node (ref "R18") (pin "1") (pinfunction "1_1") (pintype "input"))
      (node (ref "R19") (pin "1") (pinfunction "1_1") (pintype "input"))
      (node (ref "U1") (pin "9") (pinfunction "IO4_9") (pintype "input"))
    )
    (net (code "42") (name "USBDN") (class "Default")
      (node (ref "D2") (pin "1") (pinfunction "1_1") (pintype "input"))
      (node (ref "U3") (pin "6") (pinfunction "UD-_6") (pintype "input"))
      (node (ref "USBC1") (pin "A7") (pinfunction "DN1_A7") (pintype "input"))
      (node (ref "USBC1") (pin "B7") (pinfunction "DN2_B7") (pintype "input"))
    )
    (net (code "43") (name "USBDP") (class "Default")
      (node (ref "D3") (pin "1") (pinfunction "1_1") (pintype "input"))
      (node (ref "U3") (pin "5") (pinfunction "UD+_5") (pintype "input"))
      (node (ref "USBC1") (pin "A6") (pinfunction "DP1_A6") (pintype "input"))
      (node (ref "USBC1") (pin "B6") (pinfunction "DP2_B6") (pintype "input"))
    )
    (net (code "44") (name "VDD_5V") (class "Default")
      (node (ref "C5") (pin "2") (pinfunction "2_2") (pintype "input"))
      (node (ref "C8") (pin "2") (pinfunction "2_2") (pintype "input"))
      (node (ref "D4") (pin "1") (pinfunction "K_1") (pintype "input"))
      (node (ref "U2") (pin "1") (pinfunction "VIN_1") (pintype "input"))
      (node (ref "U2") (pin "3") (pinfunction "EN_3") (pintype "input"))
      (node (ref "U4") (pin "1") (pinfunction "A_1") (pintype "input"))
      (node (ref "U5") (pin "1") (pinfunction "A_1") (pintype "input"))
      (node (ref "U6") (pin "2") (pinfunction "A_2") (pintype "input"))
      (node (ref "U7") (pin "2") (pinfunction "A_2") (pintype "input"))
      (node (ref "U8") (pin "2") (pinfunction "A_2") (pintype "input"))
    )
    (net (code "45") (name "VDD_ESP32") (class "Default")
      (node (ref "C1") (pin "1") (pinfunction "1_1") (pintype "input"))
      (node (ref "C11") (pin "2") (pinfunction "2_2") (pintype "input"))
      (node (ref "C12") (pin "2") (pinfunction "2_2") (pintype "input"))
      (node (ref "C2") (pin "2") (pinfunction "2_2") (pintype "input"))
      (node (ref "C7") (pin "1") (pinfunction "1_1") (pintype "input"))
      (node (ref "LED1") (pin "2") (pinfunction "A_2") (pintype "input"))
      (node (ref "LED2") (pin "1") (pinfunction "A_1") (pintype "input"))
      (node (ref "R1") (pin "1") (pinfunction "1_1") (pintype "input"))
      (node (ref "R11") (pin "1") (pinfunction "1_1") (pintype "input"))
      (node (ref "R12") (pin "1") (pinfunction "1_1") (pintype "input"))
      (node (ref "R2") (pin "2") (pinfunction "2_2") (pintype "input"))
      (node (ref "R3") (pin "1") (pinfunction "1_1") (pintype "input"))
      (node (ref "U1") (pin "3") (pinfunction "3V3_3") (pintype "input"))
      (node (ref "U2") (pin "5") (pinfunction "VOUT_5") (pintype "input"))
      (node (ref "U3") (pin "16") (pinfunction "VCC_16") (pintype "input"))
    )
    (net (code "46") (name "VUSB") (class "Default")
      (node (ref "D1") (pin "1") (pinfunction "1_1") (pintype "input"))
      (node (ref "D4") (pin "2") (pinfunction "A_2") (pintype "input"))
      (node (ref "USBC1") (pin "A4") (pinfunction "VBUS_A4") (pintype "input"))
      (node (ref "USBC1") (pin "A9") (pinfunction "VBUS_A9") (pintype "input"))
      (node (ref "USBC1") (pin "B4") (pinfunction "VBUS_B4") (pintype "input"))
      (node (ref "USBC1") (pin "B9") (pinfunction "VBUS_B9") (pintype "input"))
    )
    (net (code "47") (name "X0") (class "Default")
      (node (ref "C15") (pin "2") (pinfunction "2_2") (pintype "input"))
      (node (ref "U3") (pin "8") (pinfunction "XO_8") (pintype "input"))
      (node (ref "X1") (pin "1") (pinfunction "OSC1_1") (pintype "input"))
    )
    (net (code "48") (name "X1") (class "Default")
      (node (ref "C14") (pin "2") (pinfunction "2_2") (pintype "input"))
      (node (ref "U3") (pin "7") (pinfunction "XI_7") (pintype "input"))
      (node (ref "X1") (pin "3") (pinfunction "OSC2_3") (pintype "input"))
    )
    (net (code "49") (name "unconnected-(U1-IO0-Pad12)") (class "Default")
      (node (ref "U1") (pin "12") (pinfunction "IO0_12") (pintype "input"))
    )
    (net (code "50") (name "unconnected-(U1-IO1-Pad13)") (class "Default")
      (node (ref "U1") (pin "13") (pinfunction "IO1_13") (pintype "input"))
    )
    (net (code "51") (name "unconnected-(U1-IO2-Pad5)") (class "Default")
      (node (ref "U1") (pin "5") (pinfunction "IO2_5") (pintype "input"))
    )
    (net (code "52") (name "unconnected-(U1-IO3-Pad6)") (class "Default")
      (node (ref "U1") (pin "6") (pinfunction "IO3_6") (pintype "input"))
    )
    (net (code "53") (name "unconnected-(U1-IO6-Pad15)") (class "Default")
      (node (ref "U1") (pin "15") (pinfunction "IO6_15") (pintype "input"))
    )
    (net (code "54") (name "unconnected-(U1-IO7-Pad16)") (class "Default")
      (node (ref "U1") (pin "16") (pinfunction "IO7_16") (pintype "input"))
    )
    (net (code "55") (name "unconnected-(U1-IO12-Pad17)") (class "Default")
      (node (ref "U1") (pin "17") (pinfunction "IO12_17") (pintype "input"))
    )
    (net (code "56") (name "unconnected-(U1-IO13-Pad18)") (class "Default")
      (node (ref "U1") (pin "18") (pinfunction "IO13_18") (pintype "input"))
    )
    (net (code "57") (name "unconnected-(U1-IO14-Pad19)") (class "Default")
      (node (ref "U1") (pin "19") (pinfunction "IO14_19") (pintype "input"))
    )
    (net (code "58") (name "unconnected-(U1-IO15-Pad20)") (class "Default")
      (node (ref "U1") (pin "20") (pinfunction "IO15_20") (pintype "input"))
    )
    (net (code "59") (name "unconnected-(U1-IO18-Pad24)") (class "Default")
      (node (ref "U1") (pin "24") (pinfunction "IO18_24") (pintype "input"))
    )
    (net (code "60") (name "unconnected-(U1-IO19-Pad25)") (class "Default")
      (node (ref "U1") (pin "25") (pinfunction "IO19_25") (pintype "input"))
    )
    (net (code "61") (name "unconnected-(U1-IO20-Pad26)") (class "Default")
      (node (ref "U1") (pin "26") (pinfunction "IO20_26") (pintype "input"))
    )
    (net (code "62") (name "unconnected-(U1-IO21-Pad27)") (class "Default")
      (node (ref "U1") (pin "27") (pinfunction "IO21_27") (pintype "input"))
    )
    (net (code "63") (name "unconnected-(U1-IO22-Pad28)") (class "Default")
      (node (ref "U1") (pin "28") (pinfunction "IO22_28") (pintype "input"))
    )
    (net (code "64") (name "unconnected-(U1-NC-Pad4)") (class "Default")
      (node (ref "U1") (pin "4") (pinfunction "NC_4") (pintype "input+no_connect"))
    )
    (net (code "65") (name "unconnected-(U1-NC-Pad7)") (class "Default")
      (node (ref "U1") (pin "7") (pinfunction "NC_7") (pintype "input+no_connect"))
    )
    (net (code "66") (name "unconnected-(U1-NC-Pad21)") (class "Default")
      (node (ref "U1") (pin "21") (pinfunction "NC_21") (pintype "input+no_connect"))
    )
    (net (code "67") (name "unconnected-(U1-NC-Pad32)") (class "Default")
      (node (ref "U1") (pin "32") (pinfunction "NC_32") (pintype "input+no_connect"))
    )
    (net (code "68") (name "unconnected-(U1-NC-Pad33)") (class "Default")
      (node (ref "U1") (pin "33") (pinfunction "NC_33") (pintype "input+no_connect"))
    )
    (net (code "69") (name "unconnected-(U1-NC-Pad34)") (class "Default")
      (node (ref "U1") (pin "34") (pinfunction "NC_34") (pintype "input+no_connect"))
    )
    (net (code "70") (name "unconnected-(U1-NC-Pad35)") (class "Default")
      (node (ref "U1") (pin "35") (pinfunction "NC_35") (pintype "input+no_connect"))
    )
    (net (code "71") (name "unconnected-(U3-CTS#-Pad9)") (class "Default")
      (node (ref "U3") (pin "9") (pinfunction "CTS#_9") (pintype "input+no_connect"))
    )
    (net (code "72") (name "unconnected-(U3-DCD#-Pad12)") (class "Default")
      (node (ref "U3") (pin "12") (pinfunction "DCD#_12") (pintype "input+no_connect"))
    )
    (net (code "73") (name "unconnected-(U3-DSR#-Pad10)") (class "Default")
      (node (ref "U3") (pin "10") (pinfunction "DSR#_10") (pintype "input+no_connect"))
    )
    (net (code "74") (name "unconnected-(U3-R232-Pad15)") (class "Default")
      (node (ref "U3") (pin "15") (pinfunction "R232_15") (pintype "input+no_connect"))
    )
    (net (code "75") (name "unconnected-(U3-RI#-Pad11)") (class "Default")
      (node (ref "U3") (pin "11") (pinfunction "RI#_11") (pintype "input+no_connect"))
    )
    (net (code "76") (name "unconnected-(U4-Pad3)") (class "Default")
      (node (ref "U4") (pin "3") (pinfunction "3_3") (pintype "input"))
    )
    (net (code "77") (name "unconnected-(U5-Pad3)") (class "Default")
      (node (ref "U5") (pin "3") (pinfunction "3_3") (pintype "input"))
    )
    (net (code "78") (name "unconnected-(U9-Pad3)") (class "Default")
      (node (ref "U9") (pin "3") (pinfunction "3_3") (pintype "input"))
    )
    (net (code "79") (name "unconnected-(U10-Pad3)") (class "Default")
      (node (ref "U10") (pin "3") (pinfunction "3_3") (pintype "input"))
    )
    (net (code "80") (name "unconnected-(U14-Pad3)") (class "Default")
      (node (ref "U14") (pin "3") (pinfunction "3_3") (pintype "input"))
    )
    (net (code "81") (name "unconnected-(U15-Pad3)") (class "Default")
      (node (ref "U15") (pin "3") (pinfunction "3_3") (pintype "input"))
    )
    (net (code "82") (name "unconnected-(USBC1-SBU1-PadA8)") (class "Default")
      (node (ref "USBC1") (pin "A8") (pinfunction "SBU1_A8") (pintype "input+no_connect"))
    )
    (net (code "83") (name "unconnected-(USBC1-SBU2-PadB8)") (class "Default")
      (node (ref "USBC1") (pin "B8") (pinfunction "SBU2_B8") (pintype "input+no_connect"))
    )
  )
)
